# MCU.net
KiCad netlist of a schematic drawn in Altium Designer
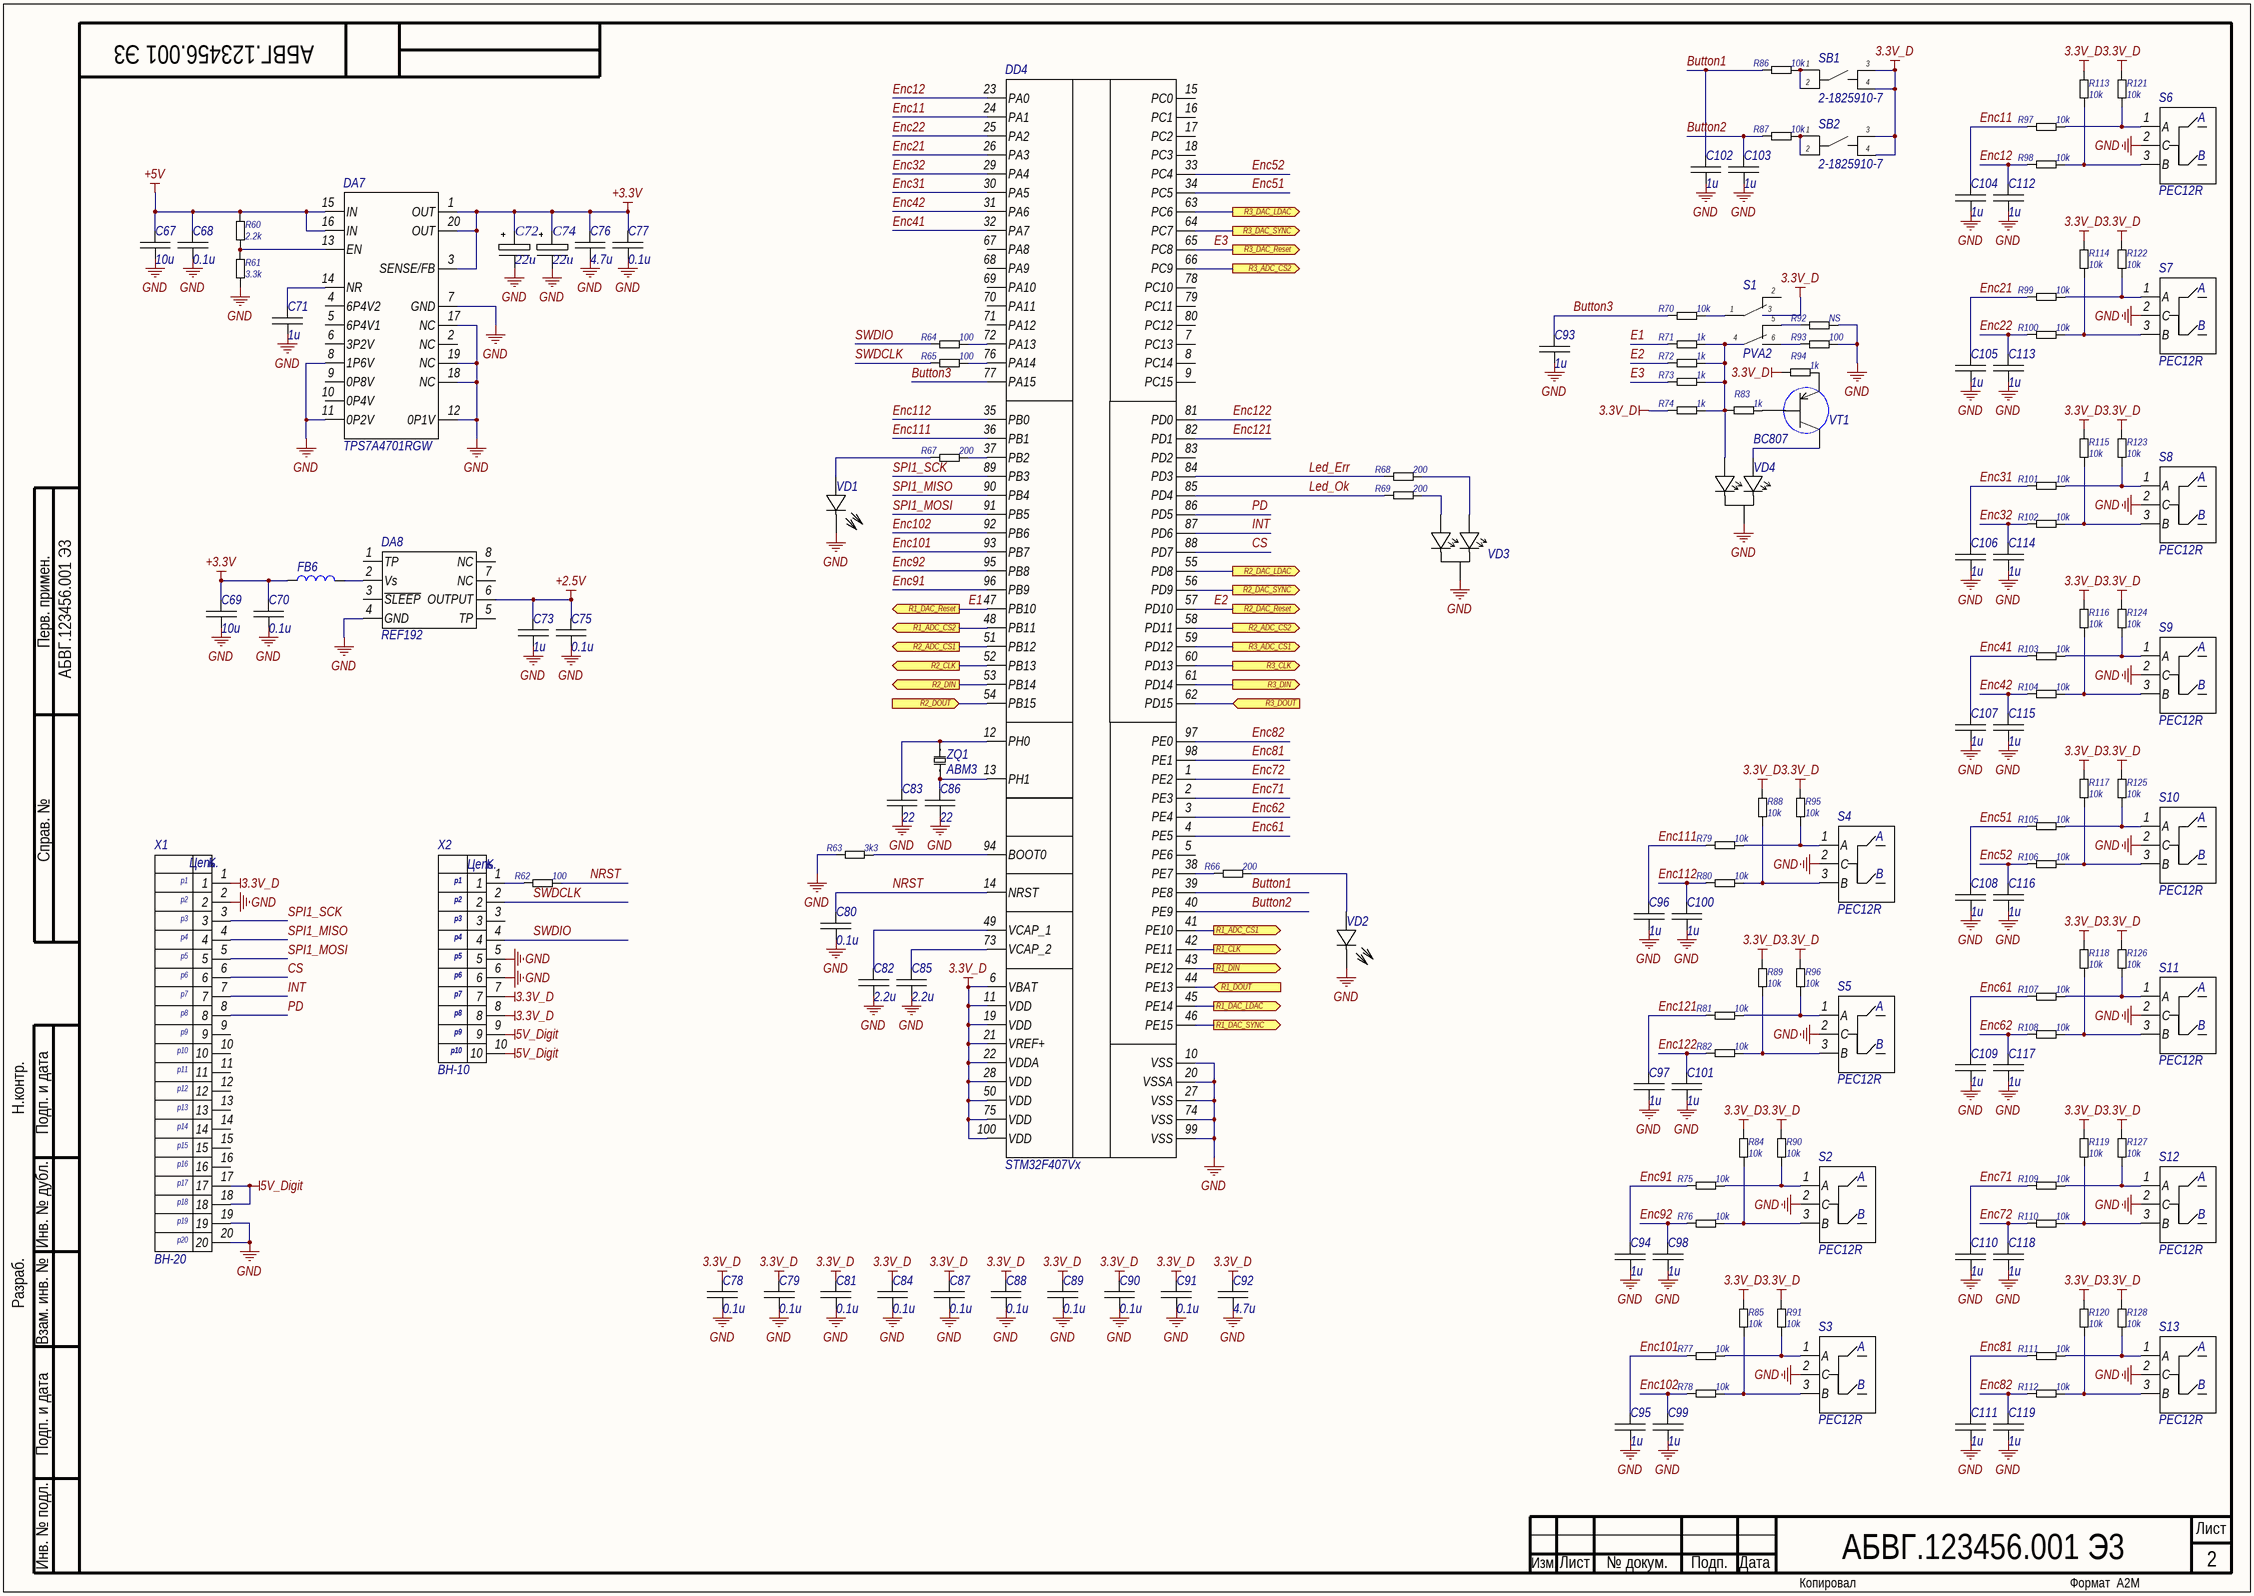
[diagram p0: MCU.SchDoc]

(export (version "E")
  (design (tool "Eeschema 10.0.6"))
  (components
    (comp (ref "C67")
      (value "10u")
      (footprint "C1206")
      (libsource (lib "ComLib") (part "Capacitor Ceramic SMD"))
    )
    (comp (ref "C68")
      (value "0.1u")
      (footprint "C0805")
      (libsource (lib "ComLib") (part "Capacitor Ceramic SMD"))
    )
    (comp (ref "C69")
      (value "10u")
      (footprint "C1206")
      (libsource (lib "ComLib") (part "Capacitor Ceramic SMD"))
    )
    (comp (ref "C70")
      (value "0.1u")
      (footprint "C0805")
      (libsource (lib "ComLib") (part "Capacitor Ceramic SMD"))
    )
    (comp (ref "C71")
      (value "1u")
      (footprint "C0805")
      (libsource (lib "ComLib") (part "Capacitor Ceramic SMD"))
    )
    (comp (ref "C72")
      (value "22u")
      (footprint "C0605")
      (libsource (lib "ComLib") (part "Capacitor Electrolytic"))
    )
    (comp (ref "C73")
      (value "1u")
      (footprint "C0805")
      (libsource (lib "ComLib") (part "Capacitor Ceramic SMD"))
    )
    (comp (ref "C74")
      (value "22u")
      (footprint "C0605")
      (libsource (lib "ComLib") (part "Capacitor Electrolytic"))
    )
    (comp (ref "C75")
      (value "0.1u")
      (footprint "C0805")
      (libsource (lib "ComLib") (part "Capacitor Ceramic SMD"))
    )
    (comp (ref "C76")
      (value "4.7u")
      (footprint "C0805")
      (libsource (lib "ComLib") (part "Capacitor Ceramic SMD"))
    )
    (comp (ref "C77")
      (value "0.1u")
      (footprint "C0805")
      (libsource (lib "ComLib") (part "Capacitor Ceramic SMD"))
    )
    (comp (ref "C78")
      (value "0.1u")
      (footprint "C0603")
      (libsource (lib "ComLib") (part "Capacitor Ceramic SMD"))
    )
    (comp (ref "C79")
      (value "0.1u")
      (footprint "C0603")
      (libsource (lib "ComLib") (part "Capacitor Ceramic SMD"))
    )
    (comp (ref "C80")
      (value "0.1u")
      (footprint "C0603")
      (libsource (lib "ComLib") (part "Capacitor Ceramic SMD"))
    )
    (comp (ref "C81")
      (value "0.1u")
      (footprint "C0603")
      (libsource (lib "ComLib") (part "Capacitor Ceramic SMD"))
    )
    (comp (ref "C82")
      (value "2.2u")
      (footprint "C0805")
      (libsource (lib "ComLib") (part "Capacitor Ceramic SMD"))
    )
    (comp (ref "C83")
      (value "22")
      (footprint "C0603")
      (libsource (lib "ComLib") (part "Capacitor Ceramic SMD"))
    )
    (comp (ref "C84")
      (value "0.1u")
      (footprint "C0603")
      (libsource (lib "ComLib") (part "Capacitor Ceramic SMD"))
    )
    (comp (ref "C85")
      (value "2.2u")
      (footprint "C0805")
      (libsource (lib "ComLib") (part "Capacitor Ceramic SMD"))
    )
    (comp (ref "C86")
      (value "22")
      (footprint "C0603")
      (libsource (lib "ComLib") (part "Capacitor Ceramic SMD"))
    )
    (comp (ref "C87")
      (value "0.1u")
      (footprint "C0603")
      (libsource (lib "ComLib") (part "Capacitor Ceramic SMD"))
    )
    (comp (ref "C88")
      (value "0.1u")
      (footprint "C0603")
      (libsource (lib "ComLib") (part "Capacitor Ceramic SMD"))
    )
    (comp (ref "C89")
      (value "0.1u")
      (footprint "C0603")
      (libsource (lib "ComLib") (part "Capacitor Ceramic SMD"))
    )
    (comp (ref "C90")
      (value "0.1u")
      (footprint "C0603")
      (libsource (lib "ComLib") (part "Capacitor Ceramic SMD"))
    )
    (comp (ref "C91")
      (value "0.1u")
      (footprint "C0603")
      (libsource (lib "ComLib") (part "Capacitor Ceramic SMD"))
    )
    (comp (ref "C92")
      (value "4.7u")
      (footprint "C0805")
      (libsource (lib "ComLib") (part "Capacitor Ceramic SMD"))
    )
    (comp (ref "C93")
      (value "1u")
      (footprint "C0805")
      (libsource (lib "ComLib") (part "Capacitor Ceramic SMD"))
    )
    (comp (ref "C94")
      (value "1u")
      (footprint "C0805")
      (libsource (lib "ComLib") (part "Capacitor Ceramic SMD"))
    )
    (comp (ref "C95")
      (value "1u")
      (footprint "C0805")
      (libsource (lib "ComLib") (part "Capacitor Ceramic SMD"))
    )
    (comp (ref "C96")
      (value "1u")
      (footprint "C0805")
      (libsource (lib "ComLib") (part "Capacitor Ceramic SMD"))
    )
    (comp (ref "C97")
      (value "1u")
      (footprint "C0805")
      (libsource (lib "ComLib") (part "Capacitor Ceramic SMD"))
    )
    (comp (ref "C98")
      (value "1u")
      (footprint "C0805")
      (libsource (lib "ComLib") (part "Capacitor Ceramic SMD"))
    )
    (comp (ref "C99")
      (value "1u")
      (footprint "C0805")
      (libsource (lib "ComLib") (part "Capacitor Ceramic SMD"))
    )
    (comp (ref "C100")
      (value "1u")
      (footprint "C0805")
      (libsource (lib "ComLib") (part "Capacitor Ceramic SMD"))
    )
    (comp (ref "C101")
      (value "1u")
      (footprint "C0805")
      (libsource (lib "ComLib") (part "Capacitor Ceramic SMD"))
    )
    (comp (ref "C102")
      (value "1u")
      (footprint "C0805")
      (libsource (lib "ComLib") (part "Capacitor Ceramic SMD"))
    )
    (comp (ref "C103")
      (value "1u")
      (footprint "C0805")
      (libsource (lib "ComLib") (part "Capacitor Ceramic SMD"))
    )
    (comp (ref "C104")
      (value "1u")
      (footprint "C0805")
      (libsource (lib "ComLib") (part "Capacitor Ceramic SMD"))
    )
    (comp (ref "C105")
      (value "1u")
      (footprint "C0805")
      (libsource (lib "ComLib") (part "Capacitor Ceramic SMD"))
    )
    (comp (ref "C106")
      (value "1u")
      (footprint "C0805")
      (libsource (lib "ComLib") (part "Capacitor Ceramic SMD"))
    )
    (comp (ref "C107")
      (value "1u")
      (footprint "C0805")
      (libsource (lib "ComLib") (part "Capacitor Ceramic SMD"))
    )
    (comp (ref "C108")
      (value "1u")
      (footprint "C0805")
      (libsource (lib "ComLib") (part "Capacitor Ceramic SMD"))
    )
    (comp (ref "C109")
      (value "1u")
      (footprint "C0805")
      (libsource (lib "ComLib") (part "Capacitor Ceramic SMD"))
    )
    (comp (ref "C110")
      (value "1u")
      (footprint "C0805")
      (libsource (lib "ComLib") (part "Capacitor Ceramic SMD"))
    )
    (comp (ref "C111")
      (value "1u")
      (footprint "C0805")
      (libsource (lib "ComLib") (part "Capacitor Ceramic SMD"))
    )
    (comp (ref "C112")
      (value "1u")
      (footprint "C0805")
      (libsource (lib "ComLib") (part "Capacitor Ceramic SMD"))
    )
    (comp (ref "C113")
      (value "1u")
      (footprint "C0805")
      (libsource (lib "ComLib") (part "Capacitor Ceramic SMD"))
    )
    (comp (ref "C114")
      (value "1u")
      (footprint "C0805")
      (libsource (lib "ComLib") (part "Capacitor Ceramic SMD"))
    )
    (comp (ref "C115")
      (value "1u")
      (footprint "C0805")
      (libsource (lib "ComLib") (part "Capacitor Ceramic SMD"))
    )
    (comp (ref "C116")
      (value "1u")
      (footprint "C0805")
      (libsource (lib "ComLib") (part "Capacitor Ceramic SMD"))
    )
    (comp (ref "C117")
      (value "1u")
      (footprint "C0805")
      (libsource (lib "ComLib") (part "Capacitor Ceramic SMD"))
    )
    (comp (ref "C118")
      (value "1u")
      (footprint "C0805")
      (libsource (lib "ComLib") (part "Capacitor Ceramic SMD"))
    )
    (comp (ref "C119")
      (value "1u")
      (footprint "C0805")
      (libsource (lib "ComLib") (part "Capacitor Ceramic SMD"))
    )
    (comp (ref "DA7")
      (value "TPS7A4701RGW")
      (footprint "QFN20 5x5")
      (libsource (lib "Librio_TS") (part "TPS7A4701RGW"))
    )
    (comp (ref "DA8") (value "REF192") (footprint "TSSOP-8_4mm") (libsource (lib "ComLib") (part "REF192")))
    (comp (ref "DD4")
      (value "STM32F407Vx")
      (footprint "LQFP100")
      (libsource (lib "Librio_TS") (part "STM32F407Vx"))
    )
    (comp (ref "FB6")
      (value "MH1608-601Y")
      (footprint "L0603")
      (libsource (lib "ComLib") (part "Ferrite Bead"))
    )
    (comp (ref "R60") (value "2.2k") (footprint "CR0805") (libsource (lib "ComLib") (part "Resistor SMD")))
    (comp (ref "R61") (value "3.3k") (footprint "CR0805") (libsource (lib "ComLib") (part "Resistor SMD")))
    (comp (ref "R62") (value "100") (footprint "CR0603") (libsource (lib "ComLib") (part "Resistor SMD")))
    (comp (ref "R63") (value "3k3") (footprint "CR0603") (libsource (lib "ComLib") (part "Resistor SMD")))
    (comp (ref "R64") (value "100") (footprint "CR0603") (libsource (lib "ComLib") (part "Resistor SMD")))
    (comp (ref "R65") (value "100") (footprint "CR0603") (libsource (lib "ComLib") (part "Resistor SMD")))
    (comp (ref "R66") (value "200") (footprint "CR0805") (libsource (lib "ComLib") (part "Resistor SMD")))
    (comp (ref "R67") (value "200") (footprint "CR0805") (libsource (lib "ComLib") (part "Resistor SMD")))
    (comp (ref "R68") (value "200") (footprint "CR0805") (libsource (lib "ComLib") (part "Resistor SMD")))
    (comp (ref "R69") (value "200") (footprint "CR0805") (libsource (lib "ComLib") (part "Resistor SMD")))
    (comp (ref "R70") (value "10k") (footprint "CR0805") (libsource (lib "ComLib") (part "Resistor SMD")))
    (comp (ref "R71") (value "1k") (footprint "CR0805") (libsource (lib "ComLib") (part "Resistor SMD")))
    (comp (ref "R72") (value "1k") (footprint "CR0805") (libsource (lib "ComLib") (part "Resistor SMD")))
    (comp (ref "R73") (value "1k") (footprint "CR0805") (libsource (lib "ComLib") (part "Resistor SMD")))
    (comp (ref "R74") (value "1k") (footprint "CR0805") (libsource (lib "ComLib") (part "Resistor SMD")))
    (comp (ref "R75") (value "10k") (footprint "CR0805") (libsource (lib "ComLib") (part "Resistor SMD")))
    (comp (ref "R76") (value "10k") (footprint "CR0805") (libsource (lib "ComLib") (part "Resistor SMD")))
    (comp (ref "R77") (value "10k") (footprint "CR0805") (libsource (lib "ComLib") (part "Resistor SMD")))
    (comp (ref "R78") (value "10k") (footprint "CR0805") (libsource (lib "ComLib") (part "Resistor SMD")))
    (comp (ref "R79") (value "10k") (footprint "CR0805") (libsource (lib "ComLib") (part "Resistor SMD")))
    (comp (ref "R80") (value "10k") (footprint "CR0805") (libsource (lib "ComLib") (part "Resistor SMD")))
    (comp (ref "R81") (value "10k") (footprint "CR0805") (libsource (lib "ComLib") (part "Resistor SMD")))
    (comp (ref "R82") (value "10k") (footprint "CR0805") (libsource (lib "ComLib") (part "Resistor SMD")))
    (comp (ref "R83") (value "1k") (footprint "CR0805") (libsource (lib "ComLib") (part "Resistor SMD")))
    (comp (ref "R84") (value "10k") (footprint "CR0805") (libsource (lib "ComLib") (part "Resistor SMD")))
    (comp (ref "R85") (value "10k") (footprint "CR0805") (libsource (lib "ComLib") (part "Resistor SMD")))
    (comp (ref "R86") (value "10k") (footprint "CR0805") (libsource (lib "ComLib") (part "Resistor SMD")))
    (comp (ref "R87") (value "10k") (footprint "CR0805") (libsource (lib "ComLib") (part "Resistor SMD")))
    (comp (ref "R88") (value "10k") (footprint "CR0805") (libsource (lib "ComLib") (part "Resistor SMD")))
    (comp (ref "R89") (value "10k") (footprint "CR0805") (libsource (lib "ComLib") (part "Resistor SMD")))
    (comp (ref "R90") (value "10k") (footprint "CR0805") (libsource (lib "ComLib") (part "Resistor SMD")))
    (comp (ref "R91") (value "10k") (footprint "CR0805") (libsource (lib "ComLib") (part "Resistor SMD")))
    (comp (ref "R92") (value "NS") (footprint "CR0805") (libsource (lib "ComLib") (part "Resistor SMD")))
    (comp (ref "R93") (value "100") (footprint "CR0805") (libsource (lib "ComLib") (part "Resistor SMD")))
    (comp (ref "R94") (value "1k") (footprint "CR0805") (libsource (lib "ComLib") (part "Resistor SMD")))
    (comp (ref "R95") (value "10k") (footprint "CR0805") (libsource (lib "ComLib") (part "Resistor SMD")))
    (comp (ref "R96") (value "10k") (footprint "CR0805") (libsource (lib "ComLib") (part "Resistor SMD")))
    (comp (ref "R97") (value "10k") (footprint "CR0805") (libsource (lib "ComLib") (part "Resistor SMD")))
    (comp (ref "R98") (value "10k") (footprint "CR0805") (libsource (lib "ComLib") (part "Resistor SMD")))
    (comp (ref "R99") (value "10k") (footprint "CR0805") (libsource (lib "ComLib") (part "Resistor SMD")))
    (comp (ref "R100") (value "10k") (footprint "CR0805") (libsource (lib "ComLib") (part "Resistor SMD")))
    (comp (ref "R101") (value "10k") (footprint "CR0805") (libsource (lib "ComLib") (part "Resistor SMD")))
    (comp (ref "R102") (value "10k") (footprint "CR0805") (libsource (lib "ComLib") (part "Resistor SMD")))
    (comp (ref "R103") (value "10k") (footprint "CR0805") (libsource (lib "ComLib") (part "Resistor SMD")))
    (comp (ref "R104") (value "10k") (footprint "CR0805") (libsource (lib "ComLib") (part "Resistor SMD")))
    (comp (ref "R105") (value "10k") (footprint "CR0805") (libsource (lib "ComLib") (part "Resistor SMD")))
    (comp (ref "R106") (value "10k") (footprint "CR0805") (libsource (lib "ComLib") (part "Resistor SMD")))
    (comp (ref "R107") (value "10k") (footprint "CR0805") (libsource (lib "ComLib") (part "Resistor SMD")))
    (comp (ref "R108") (value "10k") (footprint "CR0805") (libsource (lib "ComLib") (part "Resistor SMD")))
    (comp (ref "R109") (value "10k") (footprint "CR0805") (libsource (lib "ComLib") (part "Resistor SMD")))
    (comp (ref "R110") (value "10k") (footprint "CR0805") (libsource (lib "ComLib") (part "Resistor SMD")))
    (comp (ref "R111") (value "10k") (footprint "CR0805") (libsource (lib "ComLib") (part "Resistor SMD")))
    (comp (ref "R112") (value "10k") (footprint "CR0805") (libsource (lib "ComLib") (part "Resistor SMD")))
    (comp (ref "R113") (value "10k") (footprint "CR0805") (libsource (lib "ComLib") (part "Resistor SMD")))
    (comp (ref "R114") (value "10k") (footprint "CR0805") (libsource (lib "ComLib") (part "Resistor SMD")))
    (comp (ref "R115") (value "10k") (footprint "CR0805") (libsource (lib "ComLib") (part "Resistor SMD")))
    (comp (ref "R116") (value "10k") (footprint "CR0805") (libsource (lib "ComLib") (part "Resistor SMD")))
    (comp (ref "R117") (value "10k") (footprint "CR0805") (libsource (lib "ComLib") (part "Resistor SMD")))
    (comp (ref "R118") (value "10k") (footprint "CR0805") (libsource (lib "ComLib") (part "Resistor SMD")))
    (comp (ref "R119") (value "10k") (footprint "CR0805") (libsource (lib "ComLib") (part "Resistor SMD")))
    (comp (ref "R120") (value "10k") (footprint "CR0805") (libsource (lib "ComLib") (part "Resistor SMD")))
    (comp (ref "R121") (value "10k") (footprint "CR0805") (libsource (lib "ComLib") (part "Resistor SMD")))
    (comp (ref "R122") (value "10k") (footprint "CR0805") (libsource (lib "ComLib") (part "Resistor SMD")))
    (comp (ref "R123") (value "10k") (footprint "CR0805") (libsource (lib "ComLib") (part "Resistor SMD")))
    (comp (ref "R124") (value "10k") (footprint "CR0805") (libsource (lib "ComLib") (part "Resistor SMD")))
    (comp (ref "R125") (value "10k") (footprint "CR0805") (libsource (lib "ComLib") (part "Resistor SMD")))
    (comp (ref "R126") (value "10k") (footprint "CR0805") (libsource (lib "ComLib") (part "Resistor SMD")))
    (comp (ref "R127") (value "10k") (footprint "CR0805") (libsource (lib "ComLib") (part "Resistor SMD")))
    (comp (ref "R128") (value "10k") (footprint "CR0805") (libsource (lib "ComLib") (part "Resistor SMD")))
    (comp (ref "S1") (value "PVA2") (footprint "PVA2") (libsource (lib "ComLib") (part "Switch - Push-Push")))
    (comp (ref "S2")
      (value "PEC12R")
      (footprint "PEC12R")
      (libsource (lib "ComLib") (part "Encoder incremental"))
    )
    (comp (ref "S3")
      (value "PEC12R")
      (footprint "PEC12R")
      (libsource (lib "ComLib") (part "Encoder incremental"))
    )
    (comp (ref "S4")
      (value "PEC12R")
      (footprint "PEC12R")
      (libsource (lib "ComLib") (part "Encoder incremental"))
    )
    (comp (ref "S5")
      (value "PEC12R")
      (footprint "PEC12R")
      (libsource (lib "ComLib") (part "Encoder incremental"))
    )
    (comp (ref "S6")
      (value "PEC12R")
      (footprint "PEC12R")
      (libsource (lib "ComLib") (part "Encoder incremental"))
    )
    (comp (ref "S7")
      (value "PEC12R")
      (footprint "PEC12R")
      (libsource (lib "ComLib") (part "Encoder incremental"))
    )
    (comp (ref "S8")
      (value "PEC12R")
      (footprint "PEC12R")
      (libsource (lib "ComLib") (part "Encoder incremental"))
    )
    (comp (ref "S9")
      (value "PEC12R")
      (footprint "PEC12R")
      (libsource (lib "ComLib") (part "Encoder incremental"))
    )
    (comp (ref "S10")
      (value "PEC12R")
      (footprint "PEC12R")
      (libsource (lib "ComLib") (part "Encoder incremental"))
    )
    (comp (ref "S11")
      (value "PEC12R")
      (footprint "PEC12R")
      (libsource (lib "ComLib") (part "Encoder incremental"))
    )
    (comp (ref "S12")
      (value "PEC12R")
      (footprint "PEC12R")
      (libsource (lib "ComLib") (part "Encoder incremental"))
    )
    (comp (ref "S13")
      (value "PEC12R")
      (footprint "PEC12R")
      (libsource (lib "ComLib") (part "Encoder incremental"))
    )
    (comp (ref "SB1")
      (value "2-1825910-7")
      (footprint "Tactile_Button")
      (libsource (lib "Librio_TS") (part "Tactile Button"))
    )
    (comp (ref "SB2")
      (value "2-1825910-7")
      (footprint "Tactile_Button")
      (libsource (lib "Librio_TS") (part "Tactile Button"))
    )
    (comp (ref "VD1") (value "0805") (footprint "led 0805") (libsource (lib "Librio_TS") (part "led 0805")))
    (comp (ref "VD2") (value "0805") (footprint "led 0805") (libsource (lib "Librio_TS") (part "led 0805")))
    (comp (ref "VD3") (value "LED_BI") (footprint "LED_BI_5mm") (libsource (lib "ComLib") (part "LED_BI")))
    (comp (ref "VD4") (value "LED_BI") (footprint "LED_BI_5mm") (libsource (lib "ComLib") (part "LED_BI")))
    (comp (ref "VT1") (value "BC807") (footprint "SOT23") (libsource (lib "tranzistors") (part "BC807")))
    (comp (ref "X1")
      (value "BH-20")
      (footprint "BH-20")
      (fields
        (field (name "ALTIUM_UNNAMED_1") "p1")
        (field (name "ALTIUM_UNNAMED_2") "p2")
        (field (name "ALTIUM_UNNAMED_3") "p3")
        (field (name "ALTIUM_UNNAMED_4") "p4")
        (field (name "ALTIUM_UNNAMED_5") "p5")
        (field (name "ALTIUM_UNNAMED_6") "p6")
        (field (name "ALTIUM_UNNAMED_7") "p7")
        (field (name "ALTIUM_UNNAMED_8") "p8")
        (field (name "ALTIUM_UNNAMED_9") "p9")
        (field (name "ALTIUM_UNNAMED_10") "p10")
        (field (name "ALTIUM_UNNAMED_11") "p11")
        (field (name "ALTIUM_UNNAMED_12") "p12")
        (field (name "ALTIUM_UNNAMED_13") "p13")
        (field (name "ALTIUM_UNNAMED_14") "p14")
        (field (name "ALTIUM_UNNAMED_15") "p15")
        (field (name "ALTIUM_UNNAMED_16") "p16")
        (field (name "ALTIUM_UNNAMED_17") "p17")
        (field (name "ALTIUM_UNNAMED_18") "p18")
        (field (name "ALTIUM_UNNAMED_19") "p19")
        (field (name "ALTIUM_UNNAMED_20") "p20")
      )
      (libsource (lib "ComLib") (part "BH-20"))
    )
    (comp (ref "X2")
      (value "BH-10")
      (footprint "BH-10")
      (fields
        (field (name "ALTIUM_UNNAMED_1") "p1")
        (field (name "ALTIUM_UNNAMED_2") "p2")
        (field (name "ALTIUM_UNNAMED_3") "p3")
        (field (name "ALTIUM_UNNAMED_4") "p4")
        (field (name "ALTIUM_UNNAMED_5") "p5")
        (field (name "ALTIUM_UNNAMED_6") "p6")
        (field (name "ALTIUM_UNNAMED_7") "p7")
        (field (name "ALTIUM_UNNAMED_8") "p8")
        (field (name "ALTIUM_UNNAMED_9") "p9")
        (field (name "ALTIUM_UNNAMED_10") "p10")
      )
      (libsource (lib "ComLib") (part "BH-10"))
    )
    (comp (ref "ZQ1") (value "ABM3") (footprint "ABM3") (libsource (lib "Librio_TS") (part "Quartz ABM3")))
  )
  (nets
    (net (code "1") (name "+2.5V") (class "Default")
      (node (ref "C73") (pin "1") (pinfunction "1_1") (pintype "passive"))
      (node (ref "C75") (pin "1") (pinfunction "1_1") (pintype "passive"))
      (node (ref "DA8") (pin "6") (pinfunction "OUTPUT_6") (pintype "passive"))
    )
    (net (code "2") (name "+3.3V") (class "Default")
      (node (ref "C69") (pin "1") (pinfunction "1_1") (pintype "passive"))
      (node (ref "C70") (pin "1") (pinfunction "1_1") (pintype "passive"))
      (node (ref "C72") (pin "1") (pinfunction "1_1") (pintype "passive"))
      (node (ref "C74") (pin "1") (pinfunction "1_1") (pintype "passive"))
      (node (ref "C76") (pin "1") (pinfunction "1_1") (pintype "passive"))
      (node (ref "C77") (pin "1") (pinfunction "1_1") (pintype "passive"))
      (node (ref "DA7") (pin "1") (pinfunction "OUT_1") (pintype "passive"))
      (node (ref "DA7") (pin "20") (pinfunction "OUT_20") (pintype "passive"))
      (node (ref "DA7") (pin "3") (pinfunction "SENSE/FB_3") (pintype "passive"))
      (node (ref "FB6") (pin "1") (pinfunction "1_1") (pintype "passive"))
    )
    (net (code "3") (name "+5V") (class "Default")
      (node (ref "C67") (pin "1") (pinfunction "1_1") (pintype "passive"))
      (node (ref "C68") (pin "1") (pinfunction "1_1") (pintype "passive"))
      (node (ref "DA7") (pin "15") (pinfunction "IN_15") (pintype "passive"))
      (node (ref "DA7") (pin "16") (pinfunction "IN_16") (pintype "passive"))
      (node (ref "R60") (pin "2") (pintype "passive"))
    )
    (net (code "4") (name "/Button1") (class "Default")
      (node (ref "C102") (pin "1") (pinfunction "1_1") (pintype "passive"))
      (node (ref "DD4") (pin "39") (pinfunction "PE8_39") (pintype "passive"))
      (node (ref "R86") (pin "1") (pintype "passive"))
    )
    (net (code "5") (name "/Button2") (class "Default")
      (node (ref "C103") (pin "1") (pinfunction "1_1") (pintype "passive"))
      (node (ref "DD4") (pin "40") (pinfunction "PE9_40") (pintype "passive"))
      (node (ref "R87") (pin "1") (pintype "passive"))
    )
    (net (code "6") (name "/Button3") (class "Default")
      (node (ref "C93") (pin "1") (pinfunction "1_1") (pintype "passive"))
      (node (ref "DD4") (pin "77") (pinfunction "PA15_77") (pintype "passive"))
      (node (ref "R70") (pin "1") (pintype "passive"))
    )
    (net (code "7") (name "/CS") (class "Default")
      (node (ref "DD4") (pin "88") (pinfunction "PD7_88") (pintype "passive"))
      (node (ref "X1") (pin "6") (pinfunction "6_6") (pintype "passive"))
    )
    (net (code "8") (name "/E1") (class "Default")
      (node (ref "DD4") (pin "47") (pinfunction "PB10_47") (pintype "passive"))
      (node (ref "R71") (pin "1") (pintype "passive"))
    )
    (net (code "9") (name "/E2") (class "Default")
      (node (ref "DD4") (pin "57") (pinfunction "PD10_57") (pintype "passive"))
      (node (ref "R72") (pin "1") (pintype "passive"))
    )
    (net (code "10") (name "/E3") (class "Default")
      (node (ref "DD4") (pin "65") (pinfunction "PC8_65") (pintype "passive"))
      (node (ref "R73") (pin "1") (pintype "passive"))
    )
    (net (code "11") (name "/Enc11") (class "Default")
      (node (ref "C104") (pin "1") (pinfunction "1_1") (pintype "passive"))
      (node (ref "DD4") (pin "24") (pinfunction "PA1_24") (pintype "passive"))
      (node (ref "R97") (pin "1") (pintype "passive"))
    )
    (net (code "12") (name "/Enc12") (class "Default")
      (node (ref "C112") (pin "1") (pinfunction "1_1") (pintype "passive"))
      (node (ref "DD4") (pin "23") (pinfunction "PA0_23") (pintype "passive"))
      (node (ref "R98") (pin "1") (pintype "passive"))
    )
    (net (code "13") (name "/Enc21") (class "Default")
      (node (ref "C105") (pin "1") (pinfunction "1_1") (pintype "passive"))
      (node (ref "DD4") (pin "26") (pinfunction "PA3_26") (pintype "passive"))
      (node (ref "R99") (pin "1") (pintype "passive"))
    )
    (net (code "14") (name "/Enc22") (class "Default")
      (node (ref "C113") (pin "1") (pinfunction "1_1") (pintype "passive"))
      (node (ref "DD4") (pin "25") (pinfunction "PA2_25") (pintype "passive"))
      (node (ref "R100") (pin "1") (pintype "passive"))
    )
    (net (code "15") (name "/Enc31") (class "Default")
      (node (ref "C106") (pin "1") (pinfunction "1_1") (pintype "passive"))
      (node (ref "DD4") (pin "30") (pinfunction "PA5_30") (pintype "passive"))
      (node (ref "R101") (pin "1") (pintype "passive"))
    )
    (net (code "16") (name "/Enc32") (class "Default")
      (node (ref "C114") (pin "1") (pinfunction "1_1") (pintype "passive"))
      (node (ref "DD4") (pin "29") (pinfunction "PA4_29") (pintype "passive"))
      (node (ref "R102") (pin "1") (pintype "passive"))
    )
    (net (code "17") (name "/Enc41") (class "Default")
      (node (ref "C107") (pin "1") (pinfunction "1_1") (pintype "passive"))
      (node (ref "DD4") (pin "32") (pinfunction "PA7_32") (pintype "passive"))
      (node (ref "R103") (pin "1") (pintype "passive"))
    )
    (net (code "18") (name "/Enc42") (class "Default")
      (node (ref "C115") (pin "1") (pinfunction "1_1") (pintype "passive"))
      (node (ref "DD4") (pin "31") (pinfunction "PA6_31") (pintype "passive"))
      (node (ref "R104") (pin "1") (pintype "passive"))
    )
    (net (code "19") (name "/Enc51") (class "Default")
      (node (ref "C108") (pin "1") (pinfunction "1_1") (pintype "passive"))
      (node (ref "DD4") (pin "34") (pinfunction "PC5_34") (pintype "passive"))
      (node (ref "R105") (pin "1") (pintype "passive"))
    )
    (net (code "20") (name "/Enc52") (class "Default")
      (node (ref "C116") (pin "1") (pinfunction "1_1") (pintype "passive"))
      (node (ref "DD4") (pin "33") (pinfunction "PC4_33") (pintype "passive"))
      (node (ref "R106") (pin "1") (pintype "passive"))
    )
    (net (code "21") (name "/Enc61") (class "Default")
      (node (ref "C109") (pin "1") (pinfunction "1_1") (pintype "passive"))
      (node (ref "DD4") (pin "4") (pinfunction "PE5_4") (pintype "passive"))
      (node (ref "R107") (pin "1") (pintype "passive"))
    )
    (net (code "22") (name "/Enc62") (class "Default")
      (node (ref "C117") (pin "1") (pinfunction "1_1") (pintype "passive"))
      (node (ref "DD4") (pin "3") (pinfunction "PE4_3") (pintype "passive"))
      (node (ref "R108") (pin "1") (pintype "passive"))
    )
    (net (code "23") (name "/Enc71") (class "Default")
      (node (ref "C110") (pin "1") (pinfunction "1_1") (pintype "passive"))
      (node (ref "DD4") (pin "2") (pinfunction "PE3_2") (pintype "passive"))
      (node (ref "R109") (pin "1") (pintype "passive"))
    )
    (net (code "24") (name "/Enc72") (class "Default")
      (node (ref "C118") (pin "1") (pinfunction "1_1") (pintype "passive"))
      (node (ref "DD4") (pin "1") (pinfunction "PE2_1") (pintype "passive"))
      (node (ref "R110") (pin "1") (pintype "passive"))
    )
    (net (code "25") (name "/Enc81") (class "Default")
      (node (ref "C111") (pin "1") (pinfunction "1_1") (pintype "passive"))
      (node (ref "DD4") (pin "98") (pinfunction "PE1_98") (pintype "passive"))
      (node (ref "R111") (pin "1") (pintype "passive"))
    )
    (net (code "26") (name "/Enc82") (class "Default")
      (node (ref "C119") (pin "1") (pinfunction "1_1") (pintype "passive"))
      (node (ref "DD4") (pin "97") (pinfunction "PE0_97") (pintype "passive"))
      (node (ref "R112") (pin "1") (pintype "passive"))
    )
    (net (code "27") (name "/Enc91") (class "Default")
      (node (ref "C94") (pin "1") (pinfunction "1_1") (pintype "passive"))
      (node (ref "DD4") (pin "96") (pinfunction "PB9_96") (pintype "passive"))
      (node (ref "R75") (pin "1") (pintype "passive"))
    )
    (net (code "28") (name "/Enc92") (class "Default")
      (node (ref "C98") (pin "1") (pinfunction "1_1") (pintype "passive"))
      (node (ref "DD4") (pin "95") (pinfunction "PB8_95") (pintype "passive"))
      (node (ref "R76") (pin "1") (pintype "passive"))
    )
    (net (code "29") (name "/Enc101") (class "Default")
      (node (ref "C95") (pin "1") (pinfunction "1_1") (pintype "passive"))
      (node (ref "DD4") (pin "93") (pinfunction "PB7_93") (pintype "passive"))
      (node (ref "R77") (pin "1") (pintype "passive"))
    )
    (net (code "30") (name "/Enc102") (class "Default")
      (node (ref "C99") (pin "1") (pinfunction "1_1") (pintype "passive"))
      (node (ref "DD4") (pin "92") (pinfunction "PB6_92") (pintype "passive"))
      (node (ref "R78") (pin "1") (pintype "passive"))
    )
    (net (code "31") (name "/Enc111") (class "Default")
      (node (ref "C96") (pin "1") (pinfunction "1_1") (pintype "passive"))
      (node (ref "DD4") (pin "36") (pinfunction "PB1_36") (pintype "passive"))
      (node (ref "R79") (pin "1") (pintype "passive"))
    )
    (net (code "32") (name "/Enc112") (class "Default")
      (node (ref "C100") (pin "1") (pinfunction "1_1") (pintype "passive"))
      (node (ref "DD4") (pin "35") (pinfunction "PB0_35") (pintype "passive"))
      (node (ref "R80") (pin "1") (pintype "passive"))
    )
    (net (code "33") (name "/Enc121") (class "Default")
      (node (ref "C97") (pin "1") (pinfunction "1_1") (pintype "passive"))
      (node (ref "DD4") (pin "82") (pinfunction "PD1_82") (pintype "passive"))
      (node (ref "R81") (pin "1") (pintype "passive"))
    )
    (net (code "34") (name "/Enc122") (class "Default")
      (node (ref "C101") (pin "1") (pinfunction "1_1") (pintype "passive"))
      (node (ref "DD4") (pin "81") (pinfunction "PD0_81") (pintype "passive"))
      (node (ref "R82") (pin "1") (pintype "passive"))
    )
    (net (code "35") (name "/INT") (class "Default")
      (node (ref "DD4") (pin "87") (pinfunction "PD6_87") (pintype "passive"))
      (node (ref "X1") (pin "7") (pinfunction "7_7") (pintype "passive"))
    )
    (net (code "36") (name "/Led_Err") (class "Default")
      (node (ref "DD4") (pin "84") (pinfunction "PD3_84") (pintype "passive"))
      (node (ref "R68") (pin "1") (pintype "passive"))
    )
    (net (code "37") (name "/Led_Ok") (class "Default")
      (node (ref "DD4") (pin "85") (pinfunction "PD4_85") (pintype "passive"))
      (node (ref "R69") (pin "1") (pintype "passive"))
    )
    (net (code "38") (name "/NRST") (class "Default")
      (node (ref "C80") (pin "1") (pinfunction "1_1") (pintype "passive"))
      (node (ref "DD4") (pin "14") (pinfunction "NRST_14") (pintype "passive"))
      (node (ref "R62") (pin "2") (pintype "passive"))
    )
    (net (code "39") (name "/PD") (class "Default")
      (node (ref "DD4") (pin "86") (pinfunction "PD5_86") (pintype "passive"))
      (node (ref "X1") (pin "8") (pinfunction "8_8") (pintype "passive"))
    )
    (net (code "40") (name "/R1_ADC_CS1") (class "Default")
      (node (ref "DD4") (pin "41") (pinfunction "PE10_41") (pintype "passive"))
    )
    (net (code "41") (name "/R1_ADC_CS2") (class "Default")
      (node (ref "DD4") (pin "48") (pinfunction "PB11_48") (pintype "passive"))
    )
    (net (code "42") (name "/R1_CLK") (class "Default")
      (node (ref "DD4") (pin "42") (pinfunction "PE11_42") (pintype "passive"))
    )
    (net (code "43") (name "/R1_DAC_LDAC") (class "Default")
      (node (ref "DD4") (pin "45") (pinfunction "PE14_45") (pintype "passive"))
    )
    (net (code "44") (name "/R1_DAC_SYNC") (class "Default")
      (node (ref "DD4") (pin "46") (pinfunction "PE15_46") (pintype "passive"))
    )
    (net (code "45") (name "/R1_DIN") (class "Default")
      (node (ref "DD4") (pin "43") (pinfunction "PE12_43") (pintype "passive"))
    )
    (net (code "46") (name "/R1_DOUT") (class "Default")
      (node (ref "DD4") (pin "44") (pinfunction "PE13_44") (pintype "passive"))
    )
    (net (code "47") (name "/R2_ADC_CS1") (class "Default")
      (node (ref "DD4") (pin "51") (pinfunction "PB12_51") (pintype "passive"))
    )
    (net (code "48") (name "/R2_ADC_CS2") (class "Default")
      (node (ref "DD4") (pin "58") (pinfunction "PD11_58") (pintype "passive"))
    )
    (net (code "49") (name "/R2_CLK") (class "Default")
      (node (ref "DD4") (pin "52") (pinfunction "PB13_52") (pintype "passive"))
    )
    (net (code "50") (name "/R2_DAC_LDAC") (class "Default")
      (node (ref "DD4") (pin "55") (pinfunction "PD8_55") (pintype "passive"))
    )
    (net (code "51") (name "/R2_DAC_SYNC") (class "Default")
      (node (ref "DD4") (pin "56") (pinfunction "PD9_56") (pintype "passive"))
    )
    (net (code "52") (name "/R2_DIN") (class "Default")
      (node (ref "DD4") (pin "53") (pinfunction "PB14_53") (pintype "passive"))
    )
    (net (code "53") (name "/R2_DOUT") (class "Default")
      (node (ref "DD4") (pin "54") (pinfunction "PB15_54") (pintype "passive"))
    )
    (net (code "54") (name "/R3_ADC_CS1") (class "Default")
      (node (ref "DD4") (pin "59") (pinfunction "PD12_59") (pintype "passive"))
    )
    (net (code "55") (name "/R3_ADC_CS2") (class "Default")
      (node (ref "DD4") (pin "66") (pinfunction "PC9_66") (pintype "passive"))
    )
    (net (code "56") (name "/R3_CLK") (class "Default")
      (node (ref "DD4") (pin "60") (pinfunction "PD13_60") (pintype "passive"))
    )
    (net (code "57") (name "/R3_DAC_LDAC") (class "Default")
      (node (ref "DD4") (pin "63") (pinfunction "PC6_63") (pintype "passive"))
    )
    (net (code "58") (name "/R3_DAC_SYNC") (class "Default")
      (node (ref "DD4") (pin "64") (pinfunction "PC7_64") (pintype "passive"))
    )
    (net (code "59") (name "/R3_DIN") (class "Default")
      (node (ref "DD4") (pin "61") (pinfunction "PD14_61") (pintype "passive"))
    )
    (net (code "60") (name "/R3_DOUT") (class "Default")
      (node (ref "DD4") (pin "62") (pinfunction "PD15_62") (pintype "passive"))
    )
    (net (code "61") (name "/SPI1_MISO") (class "Default")
      (node (ref "DD4") (pin "90") (pinfunction "PB4_90") (pintype "passive"))
      (node (ref "X1") (pin "4") (pinfunction "4_4") (pintype "passive"))
    )
    (net (code "62") (name "/SPI1_MOSI") (class "Default")
      (node (ref "DD4") (pin "91") (pinfunction "PB5_91") (pintype "passive"))
      (node (ref "X1") (pin "5") (pinfunction "5_5") (pintype "passive"))
    )
    (net (code "63") (name "/SPI1_SCK") (class "Default")
      (node (ref "DD4") (pin "89") (pinfunction "PB3_89") (pintype "passive"))
      (node (ref "X1") (pin "3") (pinfunction "3_3") (pintype "passive"))
    )
    (net (code "64") (name "/SWDCLK") (class "Default")
      (node (ref "R65") (pin "1") (pintype "passive"))
      (node (ref "X2") (pin "2") (pinfunction "2_2") (pintype "passive"))
    )
    (net (code "65") (name "/SWDIO") (class "Default")
      (node (ref "R64") (pin "1") (pintype "passive"))
      (node (ref "X2") (pin "4") (pinfunction "4_4") (pintype "passive"))
    )
    (net (code "66") (name "3.3V_D") (class "Default")
      (node (ref "C78") (pin "1") (pinfunction "1_1") (pintype "passive"))
      (node (ref "C79") (pin "1") (pinfunction "1_1") (pintype "passive"))
      (node (ref "C81") (pin "1") (pinfunction "1_1") (pintype "passive"))
      (node (ref "C84") (pin "1") (pinfunction "1_1") (pintype "passive"))
      (node (ref "C87") (pin "1") (pinfunction "1_1") (pintype "passive"))
      (node (ref "C88") (pin "1") (pinfunction "1_1") (pintype "passive"))
      (node (ref "C89") (pin "1") (pinfunction "1_1") (pintype "passive"))
      (node (ref "C90") (pin "1") (pinfunction "1_1") (pintype "passive"))
      (node (ref "C91") (pin "1") (pinfunction "1_1") (pintype "passive"))
      (node (ref "C92") (pin "1") (pinfunction "1_1") (pintype "passive"))
      (node (ref "DD4") (pin "100") (pinfunction "VDD_100") (pintype "passive"))
      (node (ref "DD4") (pin "11") (pinfunction "VDD_11") (pintype "passive"))
      (node (ref "DD4") (pin "19") (pinfunction "VDD_19") (pintype "passive"))
      (node (ref "DD4") (pin "21") (pinfunction "VREF+_21") (pintype "passive"))
      (node (ref "DD4") (pin "22") (pinfunction "VDDA_22") (pintype "passive"))
      (node (ref "DD4") (pin "28") (pinfunction "VDD_28") (pintype "passive"))
      (node (ref "DD4") (pin "50") (pinfunction "VDD_50") (pintype "passive"))
      (node (ref "DD4") (pin "6") (pinfunction "VBAT_6") (pintype "passive"))
      (node (ref "DD4") (pin "75") (pinfunction "VDD_75") (pintype "passive"))
      (node (ref "R113") (pin "2") (pintype "passive"))
      (node (ref "R114") (pin "2") (pintype "passive"))
      (node (ref "R115") (pin "2") (pintype "passive"))
      (node (ref "R116") (pin "2") (pintype "passive"))
      (node (ref "R117") (pin "2") (pintype "passive"))
      (node (ref "R118") (pin "2") (pintype "passive"))
      (node (ref "R119") (pin "2") (pintype "passive"))
      (node (ref "R120") (pin "2") (pintype "passive"))
      (node (ref "R121") (pin "2") (pintype "passive"))
      (node (ref "R122") (pin "2") (pintype "passive"))
      (node (ref "R123") (pin "2") (pintype "passive"))
      (node (ref "R124") (pin "2") (pintype "passive"))
      (node (ref "R125") (pin "2") (pintype "passive"))
      (node (ref "R126") (pin "2") (pintype "passive"))
      (node (ref "R127") (pin "2") (pintype "passive"))
      (node (ref "R128") (pin "2") (pintype "passive"))
      (node (ref "R74") (pin "1") (pintype "passive"))
      (node (ref "R84") (pin "2") (pintype "passive"))
      (node (ref "R85") (pin "2") (pintype "passive"))
      (node (ref "R88") (pin "2") (pintype "passive"))
      (node (ref "R89") (pin "2") (pintype "passive"))
      (node (ref "R90") (pin "2") (pintype "passive"))
      (node (ref "R91") (pin "2") (pintype "passive"))
      (node (ref "R94") (pin "1") (pintype "passive"))
      (node (ref "R95") (pin "2") (pintype "passive"))
      (node (ref "R96") (pin "2") (pintype "passive"))
      (node (ref "S1") (pin "3") (pinfunction "3_3") (pintype "passive"))
      (node (ref "SB1") (pin "3") (pinfunction "3_3") (pintype "passive"))
      (node (ref "SB1") (pin "4") (pinfunction "4_4") (pintype "passive"))
      (node (ref "SB2") (pin "3") (pinfunction "3_3") (pintype "passive"))
      (node (ref "SB2") (pin "4") (pinfunction "4_4") (pintype "passive"))
      (node (ref "X1") (pin "1") (pinfunction "1_1") (pintype "passive"))
      (node (ref "X2") (pin "7") (pinfunction "7_7") (pintype "passive"))
      (node (ref "X2") (pin "8") (pinfunction "8_8") (pintype "passive"))
    )
    (net (code "67") (name "5V_Digit") (class "Default")
      (node (ref "X1") (pin "17") (pinfunction "17_17") (pintype "passive"))
      (node (ref "X1") (pin "18") (pinfunction "18_18") (pintype "passive"))
      (node (ref "X2") (pin "10") (pinfunction "10_10") (pintype "passive"))
      (node (ref "X2") (pin "9") (pinfunction "9_9") (pintype "passive"))
    )
    (net (code "68") (name "GND") (class "Default")
      (node (ref "C100") (pin "2") (pinfunction "2_2") (pintype "passive"))
      (node (ref "C101") (pin "2") (pinfunction "2_2") (pintype "passive"))
      (node (ref "C102") (pin "2") (pinfunction "2_2") (pintype "passive"))
      (node (ref "C103") (pin "2") (pinfunction "2_2") (pintype "passive"))
      (node (ref "C104") (pin "2") (pinfunction "2_2") (pintype "passive"))
      (node (ref "C105") (pin "2") (pinfunction "2_2") (pintype "passive"))
      (node (ref "C106") (pin "2") (pinfunction "2_2") (pintype "passive"))
      (node (ref "C107") (pin "2") (pinfunction "2_2") (pintype "passive"))
      (node (ref "C108") (pin "2") (pinfunction "2_2") (pintype "passive"))
      (node (ref "C109") (pin "2") (pinfunction "2_2") (pintype "passive"))
      (node (ref "C110") (pin "2") (pinfunction "2_2") (pintype "passive"))
      (node (ref "C111") (pin "2") (pinfunction "2_2") (pintype "passive"))
      (node (ref "C112") (pin "2") (pinfunction "2_2") (pintype "passive"))
      (node (ref "C113") (pin "2") (pinfunction "2_2") (pintype "passive"))
      (node (ref "C114") (pin "2") (pinfunction "2_2") (pintype "passive"))
      (node (ref "C115") (pin "2") (pinfunction "2_2") (pintype "passive"))
      (node (ref "C116") (pin "2") (pinfunction "2_2") (pintype "passive"))
      (node (ref "C117") (pin "2") (pinfunction "2_2") (pintype "passive"))
      (node (ref "C118") (pin "2") (pinfunction "2_2") (pintype "passive"))
      (node (ref "C119") (pin "2") (pinfunction "2_2") (pintype "passive"))
      (node (ref "C67") (pin "2") (pinfunction "2_2") (pintype "passive"))
      (node (ref "C68") (pin "2") (pinfunction "2_2") (pintype "passive"))
      (node (ref "C69") (pin "2") (pinfunction "2_2") (pintype "passive"))
      (node (ref "C70") (pin "2") (pinfunction "2_2") (pintype "passive"))
      (node (ref "C71") (pin "2") (pinfunction "2_2") (pintype "passive"))
      (node (ref "C72") (pin "2") (pinfunction "2_2") (pintype "passive"))
      (node (ref "C73") (pin "2") (pinfunction "2_2") (pintype "passive"))
      (node (ref "C74") (pin "2") (pinfunction "2_2") (pintype "passive"))
      (node (ref "C75") (pin "2") (pinfunction "2_2") (pintype "passive"))
      (node (ref "C76") (pin "2") (pinfunction "2_2") (pintype "passive"))
      (node (ref "C77") (pin "2") (pinfunction "2_2") (pintype "passive"))
      (node (ref "C78") (pin "2") (pinfunction "2_2") (pintype "passive"))
      (node (ref "C79") (pin "2") (pinfunction "2_2") (pintype "passive"))
      (node (ref "C80") (pin "2") (pinfunction "2_2") (pintype "passive"))
      (node (ref "C81") (pin "2") (pinfunction "2_2") (pintype "passive"))
      (node (ref "C82") (pin "2") (pinfunction "2_2") (pintype "passive"))
      (node (ref "C83") (pin "2") (pinfunction "2_2") (pintype "passive"))
      (node (ref "C84") (pin "2") (pinfunction "2_2") (pintype "passive"))
      (node (ref "C85") (pin "2") (pinfunction "2_2") (pintype "passive"))
      (node (ref "C86") (pin "2") (pinfunction "2_2") (pintype "passive"))
      (node (ref "C87") (pin "2") (pinfunction "2_2") (pintype "passive"))
      (node (ref "C88") (pin "2") (pinfunction "2_2") (pintype "passive"))
      (node (ref "C89") (pin "2") (pinfunction "2_2") (pintype "passive"))
      (node (ref "C90") (pin "2") (pinfunction "2_2") (pintype "passive"))
      (node (ref "C91") (pin "2") (pinfunction "2_2") (pintype "passive"))
      (node (ref "C92") (pin "2") (pinfunction "2_2") (pintype "passive"))
      (node (ref "C93") (pin "2") (pinfunction "2_2") (pintype "passive"))
      (node (ref "C94") (pin "2") (pinfunction "2_2") (pintype "passive"))
      (node (ref "C95") (pin "2") (pinfunction "2_2") (pintype "passive"))
      (node (ref "C96") (pin "2") (pinfunction "2_2") (pintype "passive"))
      (node (ref "C97") (pin "2") (pinfunction "2_2") (pintype "passive"))
      (node (ref "C98") (pin "2") (pinfunction "2_2") (pintype "passive"))
      (node (ref "C99") (pin "2") (pinfunction "2_2") (pintype "passive"))
      (node (ref "DA7") (pin "11") (pinfunction "0P2V_11") (pintype "passive"))
      (node (ref "DA7") (pin "12") (pinfunction "0P1V_12") (pintype "passive"))
      (node (ref "DA7") (pin "17") (pinfunction "NC_17") (pintype "passive"))
      (node (ref "DA7") (pin "18") (pinfunction "NC_18") (pintype "passive"))
      (node (ref "DA7") (pin "19") (pinfunction "NC_19") (pintype "passive"))
      (node (ref "DA7") (pin "7") (pinfunction "GND_7") (pintype "passive"))
      (node (ref "DA7") (pin "8") (pinfunction "1P6V_8") (pintype "passive"))
      (node (ref "DA8") (pin "4") (pinfunction "GND_4") (pintype "passive"))
      (node (ref "DD4") (pin "10") (pinfunction "VSS_10") (pintype "passive"))
      (node (ref "DD4") (pin "20") (pinfunction "VSSA_20") (pintype "passive"))
      (node (ref "DD4") (pin "27") (pinfunction "VSS_27") (pintype "passive"))
      (node (ref "DD4") (pin "74") (pinfunction "VSS_74") (pintype "passive"))
      (node (ref "DD4") (pin "99") (pinfunction "VSS_99") (pintype "passive"))
      (node (ref "R61") (pin "1") (pintype "passive"))
      (node (ref "R63") (pin "1") (pintype "passive"))
      (node (ref "R92") (pin "2") (pintype "passive"))
      (node (ref "R93") (pin "2") (pintype "passive"))
      (node (ref "S10") (pin "2") (pinfunction "C_2") (pintype "passive"))
      (node (ref "S11") (pin "2") (pinfunction "C_2") (pintype "passive"))
      (node (ref "S12") (pin "2") (pinfunction "C_2") (pintype "passive"))
      (node (ref "S13") (pin "2") (pinfunction "C_2") (pintype "passive"))
      (node (ref "S2") (pin "2") (pinfunction "C_2") (pintype "passive"))
      (node (ref "S3") (pin "2") (pinfunction "C_2") (pintype "passive"))
      (node (ref "S4") (pin "2") (pinfunction "C_2") (pintype "passive"))
      (node (ref "S5") (pin "2") (pinfunction "C_2") (pintype "passive"))
      (node (ref "S6") (pin "2") (pinfunction "C_2") (pintype "passive"))
      (node (ref "S7") (pin "2") (pinfunction "C_2") (pintype "passive"))
      (node (ref "S8") (pin "2") (pinfunction "C_2") (pintype "passive"))
      (node (ref "S9") (pin "2") (pinfunction "C_2") (pintype "passive"))
      (node (ref "VD1") (pin "2") (pinfunction "2_2") (pintype "passive"))
      (node (ref "VD2") (pin "2") (pinfunction "2_2") (pintype "passive"))
      (node (ref "VD3") (pin "2") (pinfunction "2_2") (pintype "passive"))
      (node (ref "VD4") (pin "2") (pinfunction "2_2") (pintype "passive"))
      (node (ref "X1") (pin "19") (pinfunction "19_19") (pintype "passive"))
      (node (ref "X1") (pin "2") (pinfunction "2_2") (pintype "passive"))
      (node (ref "X1") (pin "20") (pinfunction "20_20") (pintype "passive"))
      (node (ref "X2") (pin "5") (pinfunction "5_5") (pintype "passive"))
      (node (ref "X2") (pin "6") (pinfunction "6_6") (pintype "passive"))
    )
    (net (code "69") (name "Net-(DA7-EN)") (class "Default")
      (node (ref "DA7") (pin "13") (pinfunction "EN_13") (pintype "passive"))
      (node (ref "R60") (pin "1") (pintype "passive"))
      (node (ref "R61") (pin "2") (pintype "passive"))
    )
    (net (code "70") (name "Net-(DA7-NR)") (class "Default")
      (node (ref "C71") (pin "1") (pinfunction "1_1") (pintype "passive"))
      (node (ref "DA7") (pin "14") (pinfunction "NR_14") (pintype "passive"))
    )
    (net (code "71") (name "Net-(DA8-Vs)") (class "Default")
      (node (ref "DA8") (pin "2") (pinfunction "Vs_2") (pintype "passive"))
      (node (ref "FB6") (pin "2") (pinfunction "2_2") (pintype "passive"))
    )
    (net (code "72") (name "Net-(DD4-BOOT0)") (class "Default")
      (node (ref "DD4") (pin "94") (pinfunction "BOOT0_94") (pintype "passive"))
      (node (ref "R63") (pin "2") (pintype "passive"))
    )
    (net (code "73") (name "Net-(DD4-PA13)") (class "Default")
      (node (ref "DD4") (pin "72") (pinfunction "PA13_72") (pintype "passive"))
      (node (ref "R64") (pin "2") (pintype "passive"))
    )
    (net (code "74") (name "Net-(DD4-PA14)") (class "Default")
      (node (ref "DD4") (pin "76") (pinfunction "PA14_76") (pintype "passive"))
      (node (ref "R65") (pin "2") (pintype "passive"))
    )
    (net (code "75") (name "Net-(DD4-PB2)") (class "Default")
      (node (ref "DD4") (pin "37") (pinfunction "PB2_37") (pintype "passive"))
      (node (ref "R67") (pin "1") (pintype "passive"))
    )
    (net (code "76") (name "Net-(DD4-PE7)") (class "Default")
      (node (ref "DD4") (pin "38") (pinfunction "PE7_38") (pintype "passive"))
      (node (ref "R66") (pin "2") (pintype "passive"))
    )
    (net (code "77") (name "Net-(DD4-PH0)") (class "Default")
      (node (ref "C83") (pin "1") (pinfunction "1_1") (pintype "passive"))
      (node (ref "DD4") (pin "12") (pinfunction "PH0_12") (pintype "passive"))
      (node (ref "ZQ1") (pin "2") (pinfunction "2_2") (pintype "passive"))
    )
    (net (code "78") (name "Net-(DD4-PH1)") (class "Default")
      (node (ref "C86") (pin "1") (pinfunction "1_1") (pintype "passive"))
      (node (ref "DD4") (pin "13") (pinfunction "PH1_13") (pintype "passive"))
      (node (ref "ZQ1") (pin "1") (pinfunction "1_1") (pintype "passive"))
    )
    (net (code "79") (name "Net-(DD4-VCAP_1)") (class "Default")
      (node (ref "C82") (pin "1") (pinfunction "1_1") (pintype "passive"))
      (node (ref "DD4") (pin "49") (pinfunction "VCAP_1_49") (pintype "passive"))
    )
    (net (code "80") (name "Net-(DD4-VCAP_2)") (class "Default")
      (node (ref "C85") (pin "1") (pinfunction "1_1") (pintype "passive"))
      (node (ref "DD4") (pin "73") (pinfunction "VCAP_2_73") (pintype "passive"))
    )
    (net (code "81") (name "Net-(R62-Pad1)") (class "Default")
      (node (ref "R62") (pin "1") (pintype "passive"))
      (node (ref "X2") (pin "1") (pinfunction "1_1") (pintype "passive"))
    )
    (net (code "82") (name "Net-(R66-Pad1)") (class "Default")
      (node (ref "R66") (pin "1") (pintype "passive"))
      (node (ref "VD2") (pin "1") (pinfunction "1_1") (pintype "passive"))
    )
    (net (code "83") (name "Net-(R67-Pad2)") (class "Default")
      (node (ref "R67") (pin "2") (pintype "passive"))
      (node (ref "VD1") (pin "1") (pinfunction "1_1") (pintype "passive"))
    )
    (net (code "84") (name "Net-(R68-Pad2)") (class "Default")
      (node (ref "R68") (pin "2") (pintype "passive"))
      (node (ref "VD3") (pin "1") (pinfunction "1_1") (pintype "passive"))
    )
    (net (code "85") (name "Net-(R69-Pad2)") (class "Default")
      (node (ref "R69") (pin "2") (pintype "passive"))
      (node (ref "VD3") (pin "3") (pinfunction "3_3") (pintype "passive"))
    )
    (net (code "86") (name "Net-(R70-Pad2)") (class "Default")
      (node (ref "R70") (pin "2") (pintype "passive"))
      (node (ref "S1") (pin "1") (pinfunction "1_1") (pintype "passive"))
    )
    (net (code "87") (name "Net-(R71-Pad2)") (class "Default")
      (node (ref "R71") (pin "2") (pintype "passive"))
      (node (ref "R72") (pin "2") (pintype "passive"))
      (node (ref "R73") (pin "2") (pintype "passive"))
      (node (ref "R74") (pin "2") (pintype "passive"))
      (node (ref "R83") (pin "1") (pintype "passive"))
      (node (ref "S1") (pin "4") (pinfunction "4_4") (pintype "passive"))
      (node (ref "VD4") (pin "3") (pinfunction "3_3") (pintype "passive"))
    )
    (net (code "88") (name "Net-(R83-Pad2)") (class "Default")
      (node (ref "R83") (pin "2") (pintype "passive"))
      (node (ref "VT1") (pin "1") (pinfunction "1_1") (pintype "passive"))
    )
    (net (code "89") (name "Net-(R86-Pad2)") (class "Default")
      (node (ref "R86") (pin "2") (pintype "passive"))
      (node (ref "SB1") (pin "1") (pinfunction "1_1") (pintype "passive"))
      (node (ref "SB1") (pin "2") (pinfunction "2_2") (pintype "passive"))
    )
    (net (code "90") (name "Net-(R87-Pad2)") (class "Default")
      (node (ref "R87") (pin "2") (pintype "passive"))
      (node (ref "SB2") (pin "1") (pinfunction "1_1") (pintype "passive"))
      (node (ref "SB2") (pin "2") (pinfunction "2_2") (pintype "passive"))
    )
    (net (code "91") (name "Net-(R92-Pad1)") (class "Default")
      (node (ref "R92") (pin "1") (pintype "passive"))
      (node (ref "S1") (pin "5") (pinfunction "5_5") (pintype "passive"))
    )
    (net (code "92") (name "Net-(R93-Pad1)") (class "Default")
      (node (ref "R93") (pin "1") (pintype "passive"))
      (node (ref "S1") (pin "6") (pinfunction "6_6") (pintype "passive"))
    )
    (net (code "93") (name "Net-(R94-Pad2)") (class "Default")
      (node (ref "R94") (pin "2") (pintype "passive"))
      (node (ref "VT1") (pin "2") (pinfunction "2_2") (pintype "passive"))
    )
    (net (code "94") (name "Net-(S2-A)") (class "Default")
      (node (ref "R75") (pin "2") (pintype "passive"))
      (node (ref "R90") (pin "1") (pintype "passive"))
      (node (ref "S2") (pin "1") (pinfunction "A_1") (pintype "passive"))
    )
    (net (code "95") (name "Net-(S2-B)") (class "Default")
      (node (ref "R76") (pin "2") (pintype "passive"))
      (node (ref "R84") (pin "1") (pintype "passive"))
      (node (ref "S2") (pin "3") (pinfunction "B_3") (pintype "passive"))
    )
    (net (code "96") (name "Net-(S3-A)") (class "Default")
      (node (ref "R77") (pin "2") (pintype "passive"))
      (node (ref "R91") (pin "1") (pintype "passive"))
      (node (ref "S3") (pin "1") (pinfunction "A_1") (pintype "passive"))
    )
    (net (code "97") (name "Net-(S3-B)") (class "Default")
      (node (ref "R78") (pin "2") (pintype "passive"))
      (node (ref "R85") (pin "1") (pintype "passive"))
      (node (ref "S3") (pin "3") (pinfunction "B_3") (pintype "passive"))
    )
    (net (code "98") (name "Net-(S4-A)") (class "Default")
      (node (ref "R79") (pin "2") (pintype "passive"))
      (node (ref "R95") (pin "1") (pintype "passive"))
      (node (ref "S4") (pin "1") (pinfunction "A_1") (pintype "passive"))
    )
    (net (code "99") (name "Net-(S4-B)") (class "Default")
      (node (ref "R80") (pin "2") (pintype "passive"))
      (node (ref "R88") (pin "1") (pintype "passive"))
      (node (ref "S4") (pin "3") (pinfunction "B_3") (pintype "passive"))
    )
    (net (code "100") (name "Net-(S5-A)") (class "Default")
      (node (ref "R81") (pin "2") (pintype "passive"))
      (node (ref "R96") (pin "1") (pintype "passive"))
      (node (ref "S5") (pin "1") (pinfunction "A_1") (pintype "passive"))
    )
    (net (code "101") (name "Net-(S5-B)") (class "Default")
      (node (ref "R82") (pin "2") (pintype "passive"))
      (node (ref "R89") (pin "1") (pintype "passive"))
      (node (ref "S5") (pin "3") (pinfunction "B_3") (pintype "passive"))
    )
    (net (code "102") (name "Net-(S6-A)") (class "Default")
      (node (ref "R121") (pin "1") (pintype "passive"))
      (node (ref "R97") (pin "2") (pintype "passive"))
      (node (ref "S6") (pin "1") (pinfunction "A_1") (pintype "passive"))
    )
    (net (code "103") (name "Net-(S6-B)") (class "Default")
      (node (ref "R113") (pin "1") (pintype "passive"))
      (node (ref "R98") (pin "2") (pintype "passive"))
      (node (ref "S6") (pin "3") (pinfunction "B_3") (pintype "passive"))
    )
    (net (code "104") (name "Net-(S7-A)") (class "Default")
      (node (ref "R122") (pin "1") (pintype "passive"))
      (node (ref "R99") (pin "2") (pintype "passive"))
      (node (ref "S7") (pin "1") (pinfunction "A_1") (pintype "passive"))
    )
    (net (code "105") (name "Net-(S7-B)") (class "Default")
      (node (ref "R100") (pin "2") (pintype "passive"))
      (node (ref "R114") (pin "1") (pintype "passive"))
      (node (ref "S7") (pin "3") (pinfunction "B_3") (pintype "passive"))
    )
    (net (code "106") (name "Net-(S8-A)") (class "Default")
      (node (ref "R101") (pin "2") (pintype "passive"))
      (node (ref "R123") (pin "1") (pintype "passive"))
      (node (ref "S8") (pin "1") (pinfunction "A_1") (pintype "passive"))
    )
    (net (code "107") (name "Net-(S8-B)") (class "Default")
      (node (ref "R102") (pin "2") (pintype "passive"))
      (node (ref "R115") (pin "1") (pintype "passive"))
      (node (ref "S8") (pin "3") (pinfunction "B_3") (pintype "passive"))
    )
    (net (code "108") (name "Net-(S9-A)") (class "Default")
      (node (ref "R103") (pin "2") (pintype "passive"))
      (node (ref "R124") (pin "1") (pintype "passive"))
      (node (ref "S9") (pin "1") (pinfunction "A_1") (pintype "passive"))
    )
    (net (code "109") (name "Net-(S9-B)") (class "Default")
      (node (ref "R104") (pin "2") (pintype "passive"))
      (node (ref "R116") (pin "1") (pintype "passive"))
      (node (ref "S9") (pin "3") (pinfunction "B_3") (pintype "passive"))
    )
    (net (code "110") (name "Net-(S10-A)") (class "Default")
      (node (ref "R105") (pin "2") (pintype "passive"))
      (node (ref "R125") (pin "1") (pintype "passive"))
      (node (ref "S10") (pin "1") (pinfunction "A_1") (pintype "passive"))
    )
    (net (code "111") (name "Net-(S10-B)") (class "Default")
      (node (ref "R106") (pin "2") (pintype "passive"))
      (node (ref "R117") (pin "1") (pintype "passive"))
      (node (ref "S10") (pin "3") (pinfunction "B_3") (pintype "passive"))
    )
    (net (code "112") (name "Net-(S11-A)") (class "Default")
      (node (ref "R107") (pin "2") (pintype "passive"))
      (node (ref "R126") (pin "1") (pintype "passive"))
      (node (ref "S11") (pin "1") (pinfunction "A_1") (pintype "passive"))
    )
    (net (code "113") (name "Net-(S11-B)") (class "Default")
      (node (ref "R108") (pin "2") (pintype "passive"))
      (node (ref "R118") (pin "1") (pintype "passive"))
      (node (ref "S11") (pin "3") (pinfunction "B_3") (pintype "passive"))
    )
    (net (code "114") (name "Net-(S12-A)") (class "Default")
      (node (ref "R109") (pin "2") (pintype "passive"))
      (node (ref "R127") (pin "1") (pintype "passive"))
      (node (ref "S12") (pin "1") (pinfunction "A_1") (pintype "passive"))
    )
    (net (code "115") (name "Net-(S12-B)") (class "Default")
      (node (ref "R110") (pin "2") (pintype "passive"))
      (node (ref "R119") (pin "1") (pintype "passive"))
      (node (ref "S12") (pin "3") (pinfunction "B_3") (pintype "passive"))
    )
    (net (code "116") (name "Net-(S13-A)") (class "Default")
      (node (ref "R111") (pin "2") (pintype "passive"))
      (node (ref "R128") (pin "1") (pintype "passive"))
      (node (ref "S13") (pin "1") (pinfunction "A_1") (pintype "passive"))
    )
    (net (code "117") (name "Net-(S13-B)") (class "Default")
      (node (ref "R112") (pin "2") (pintype "passive"))
      (node (ref "R120") (pin "1") (pintype "passive"))
      (node (ref "S13") (pin "3") (pinfunction "B_3") (pintype "passive"))
    )
    (net (code "118") (name "Net-(VD4-Pad1)") (class "Default")
      (node (ref "VD4") (pin "1") (pinfunction "1_1") (pintype "passive"))
      (node (ref "VT1") (pin "3") (pinfunction "3_3") (pintype "passive"))
    )
    (net (code "119") (name "unconnected-(DA7-0P4V-Pad10)") (class "Default")
      (node (ref "DA7") (pin "10") (pinfunction "0P4V_10") (pintype "passive"))
    )
    (net (code "120") (name "unconnected-(DA7-0P8V-Pad9)") (class "Default")
      (node (ref "DA7") (pin "9") (pinfunction "0P8V_9") (pintype "passive"))
    )
    (net (code "121") (name "unconnected-(DA7-3P2V-Pad6)") (class "Default")
      (node (ref "DA7") (pin "6") (pinfunction "3P2V_6") (pintype "passive"))
    )
    (net (code "122") (name "unconnected-(DA7-6P4V1-Pad5)") (class "Default")
      (node (ref "DA7") (pin "5") (pinfunction "6P4V1_5") (pintype "passive"))
    )
    (net (code "123") (name "unconnected-(DA7-6P4V2-Pad4)") (class "Default")
      (node (ref "DA7") (pin "4") (pinfunction "6P4V2_4") (pintype "passive"))
    )
    (net (code "124") (name "unconnected-(DA7-NC-Pad2)") (class "Default")
      (node (ref "DA7") (pin "2") (pinfunction "NC_2") (pintype "passive"))
    )
    (net (code "125") (name "unconnected-(DA8-NC-Pad7)") (class "Default")
      (node (ref "DA8") (pin "7") (pinfunction "NC_7") (pintype "passive"))
    )
    (net (code "126") (name "unconnected-(DA8-NC-Pad8)") (class "Default")
      (node (ref "DA8") (pin "8") (pinfunction "NC_8") (pintype "passive"))
    )
    (net (code "127") (name "unconnected-(DA8-TP-Pad1)") (class "Default")
      (node (ref "DA8") (pin "1") (pinfunction "TP_1") (pintype "passive"))
    )
    (net (code "128") (name "unconnected-(DA8-TP-Pad5)") (class "Default")
      (node (ref "DA8") (pin "5") (pinfunction "TP_5") (pintype "passive"))
    )
    (net (code "129") (name "unconnected-(DA8-~{SLEEP}-Pad3)") (class "Default")
      (node (ref "DA8") (pin "3") (pinfunction "~{SLEEP}_3") (pintype "passive"))
    )
    (net (code "130") (name "unconnected-(DD4-PA8-Pad67)") (class "Default")
      (node (ref "DD4") (pin "67") (pinfunction "PA8_67") (pintype "passive"))
    )
    (net (code "131") (name "unconnected-(DD4-PA9-Pad68)") (class "Default")
      (node (ref "DD4") (pin "68") (pinfunction "PA9_68") (pintype "passive"))
    )
    (net (code "132") (name "unconnected-(DD4-PA10-Pad69)") (class "Default")
      (node (ref "DD4") (pin "69") (pinfunction "PA10_69") (pintype "passive"))
    )
    (net (code "133") (name "unconnected-(DD4-PA11-Pad70)") (class "Default")
      (node (ref "DD4") (pin "70") (pinfunction "PA11_70") (pintype "passive"))
    )
    (net (code "134") (name "unconnected-(DD4-PA12-Pad71)") (class "Default")
      (node (ref "DD4") (pin "71") (pinfunction "PA12_71") (pintype "passive"))
    )
    (net (code "135") (name "unconnected-(DD4-PC0-Pad15)") (class "Default")
      (node (ref "DD4") (pin "15") (pinfunction "PC0_15") (pintype "passive"))
    )
    (net (code "136") (name "unconnected-(DD4-PC1-Pad16)") (class "Default")
      (node (ref "DD4") (pin "16") (pinfunction "PC1_16") (pintype "passive"))
    )
    (net (code "137") (name "unconnected-(DD4-PC2-Pad17)") (class "Default")
      (node (ref "DD4") (pin "17") (pinfunction "PC2_17") (pintype "passive"))
    )
    (net (code "138") (name "unconnected-(DD4-PC3-Pad18)") (class "Default")
      (node (ref "DD4") (pin "18") (pinfunction "PC3_18") (pintype "passive"))
    )
    (net (code "139") (name "unconnected-(DD4-PC10-Pad78)") (class "Default")
      (node (ref "DD4") (pin "78") (pinfunction "PC10_78") (pintype "passive"))
    )
    (net (code "140") (name "unconnected-(DD4-PC11-Pad79)") (class "Default")
      (node (ref "DD4") (pin "79") (pinfunction "PC11_79") (pintype "passive"))
    )
    (net (code "141") (name "unconnected-(DD4-PC12-Pad80)") (class "Default")
      (node (ref "DD4") (pin "80") (pinfunction "PC12_80") (pintype "passive"))
    )
    (net (code "142") (name "unconnected-(DD4-PC13-Pad7)") (class "Default")
      (node (ref "DD4") (pin "7") (pinfunction "PC13_7") (pintype "passive"))
    )
    (net (code "143") (name "unconnected-(DD4-PC14-Pad8)") (class "Default")
      (node (ref "DD4") (pin "8") (pinfunction "PC14_8") (pintype "passive"))
    )
    (net (code "144") (name "unconnected-(DD4-PC15-Pad9)") (class "Default")
      (node (ref "DD4") (pin "9") (pinfunction "PC15_9") (pintype "passive"))
    )
    (net (code "145") (name "unconnected-(DD4-PD2-Pad83)") (class "Default")
      (node (ref "DD4") (pin "83") (pinfunction "PD2_83") (pintype "passive"))
    )
    (net (code "146") (name "unconnected-(DD4-PE6-Pad5)") (class "Default")
      (node (ref "DD4") (pin "5") (pinfunction "PE6_5") (pintype "passive"))
    )
    (net (code "147") (name "unconnected-(S1-Pad2)") (class "Default")
      (node (ref "S1") (pin "2") (pinfunction "2_2") (pintype "passive"))
    )
    (net (code "148") (name "unconnected-(X1-Pad9)") (class "Default")
      (node (ref "X1") (pin "9") (pinfunction "9_9") (pintype "passive"))
    )
    (net (code "149") (name "unconnected-(X1-Pad10)") (class "Default")
      (node (ref "X1") (pin "10") (pinfunction "10_10") (pintype "passive"))
    )
    (net (code "150") (name "unconnected-(X1-Pad11)") (class "Default")
      (node (ref "X1") (pin "11") (pinfunction "11_11") (pintype "passive"))
    )
    (net (code "151") (name "unconnected-(X1-Pad12)") (class "Default")
      (node (ref "X1") (pin "12") (pinfunction "12_12") (pintype "passive"))
    )
    (net (code "152") (name "unconnected-(X1-Pad13)") (class "Default")
      (node (ref "X1") (pin "13") (pinfunction "13_13") (pintype "passive"))
    )
    (net (code "153") (name "unconnected-(X1-Pad14)") (class "Default")
      (node (ref "X1") (pin "14") (pinfunction "14_14") (pintype "passive"))
    )
    (net (code "154") (name "unconnected-(X1-Pad15)") (class "Default")
      (node (ref "X1") (pin "15") (pinfunction "15_15") (pintype "passive"))
    )
    (net (code "155") (name "unconnected-(X1-Pad16)") (class "Default")
      (node (ref "X1") (pin "16") (pinfunction "16_16") (pintype "passive"))
    )
    (net (code "156") (name "unconnected-(X2-Pad3)") (class "Default")
      (node (ref "X2") (pin "3") (pinfunction "3_3") (pintype "passive"))
    )
  )
)
